# SCH_Star_blinking_2021-12-23.net
KiCad netlist of a schematic drawn in EasyEDA
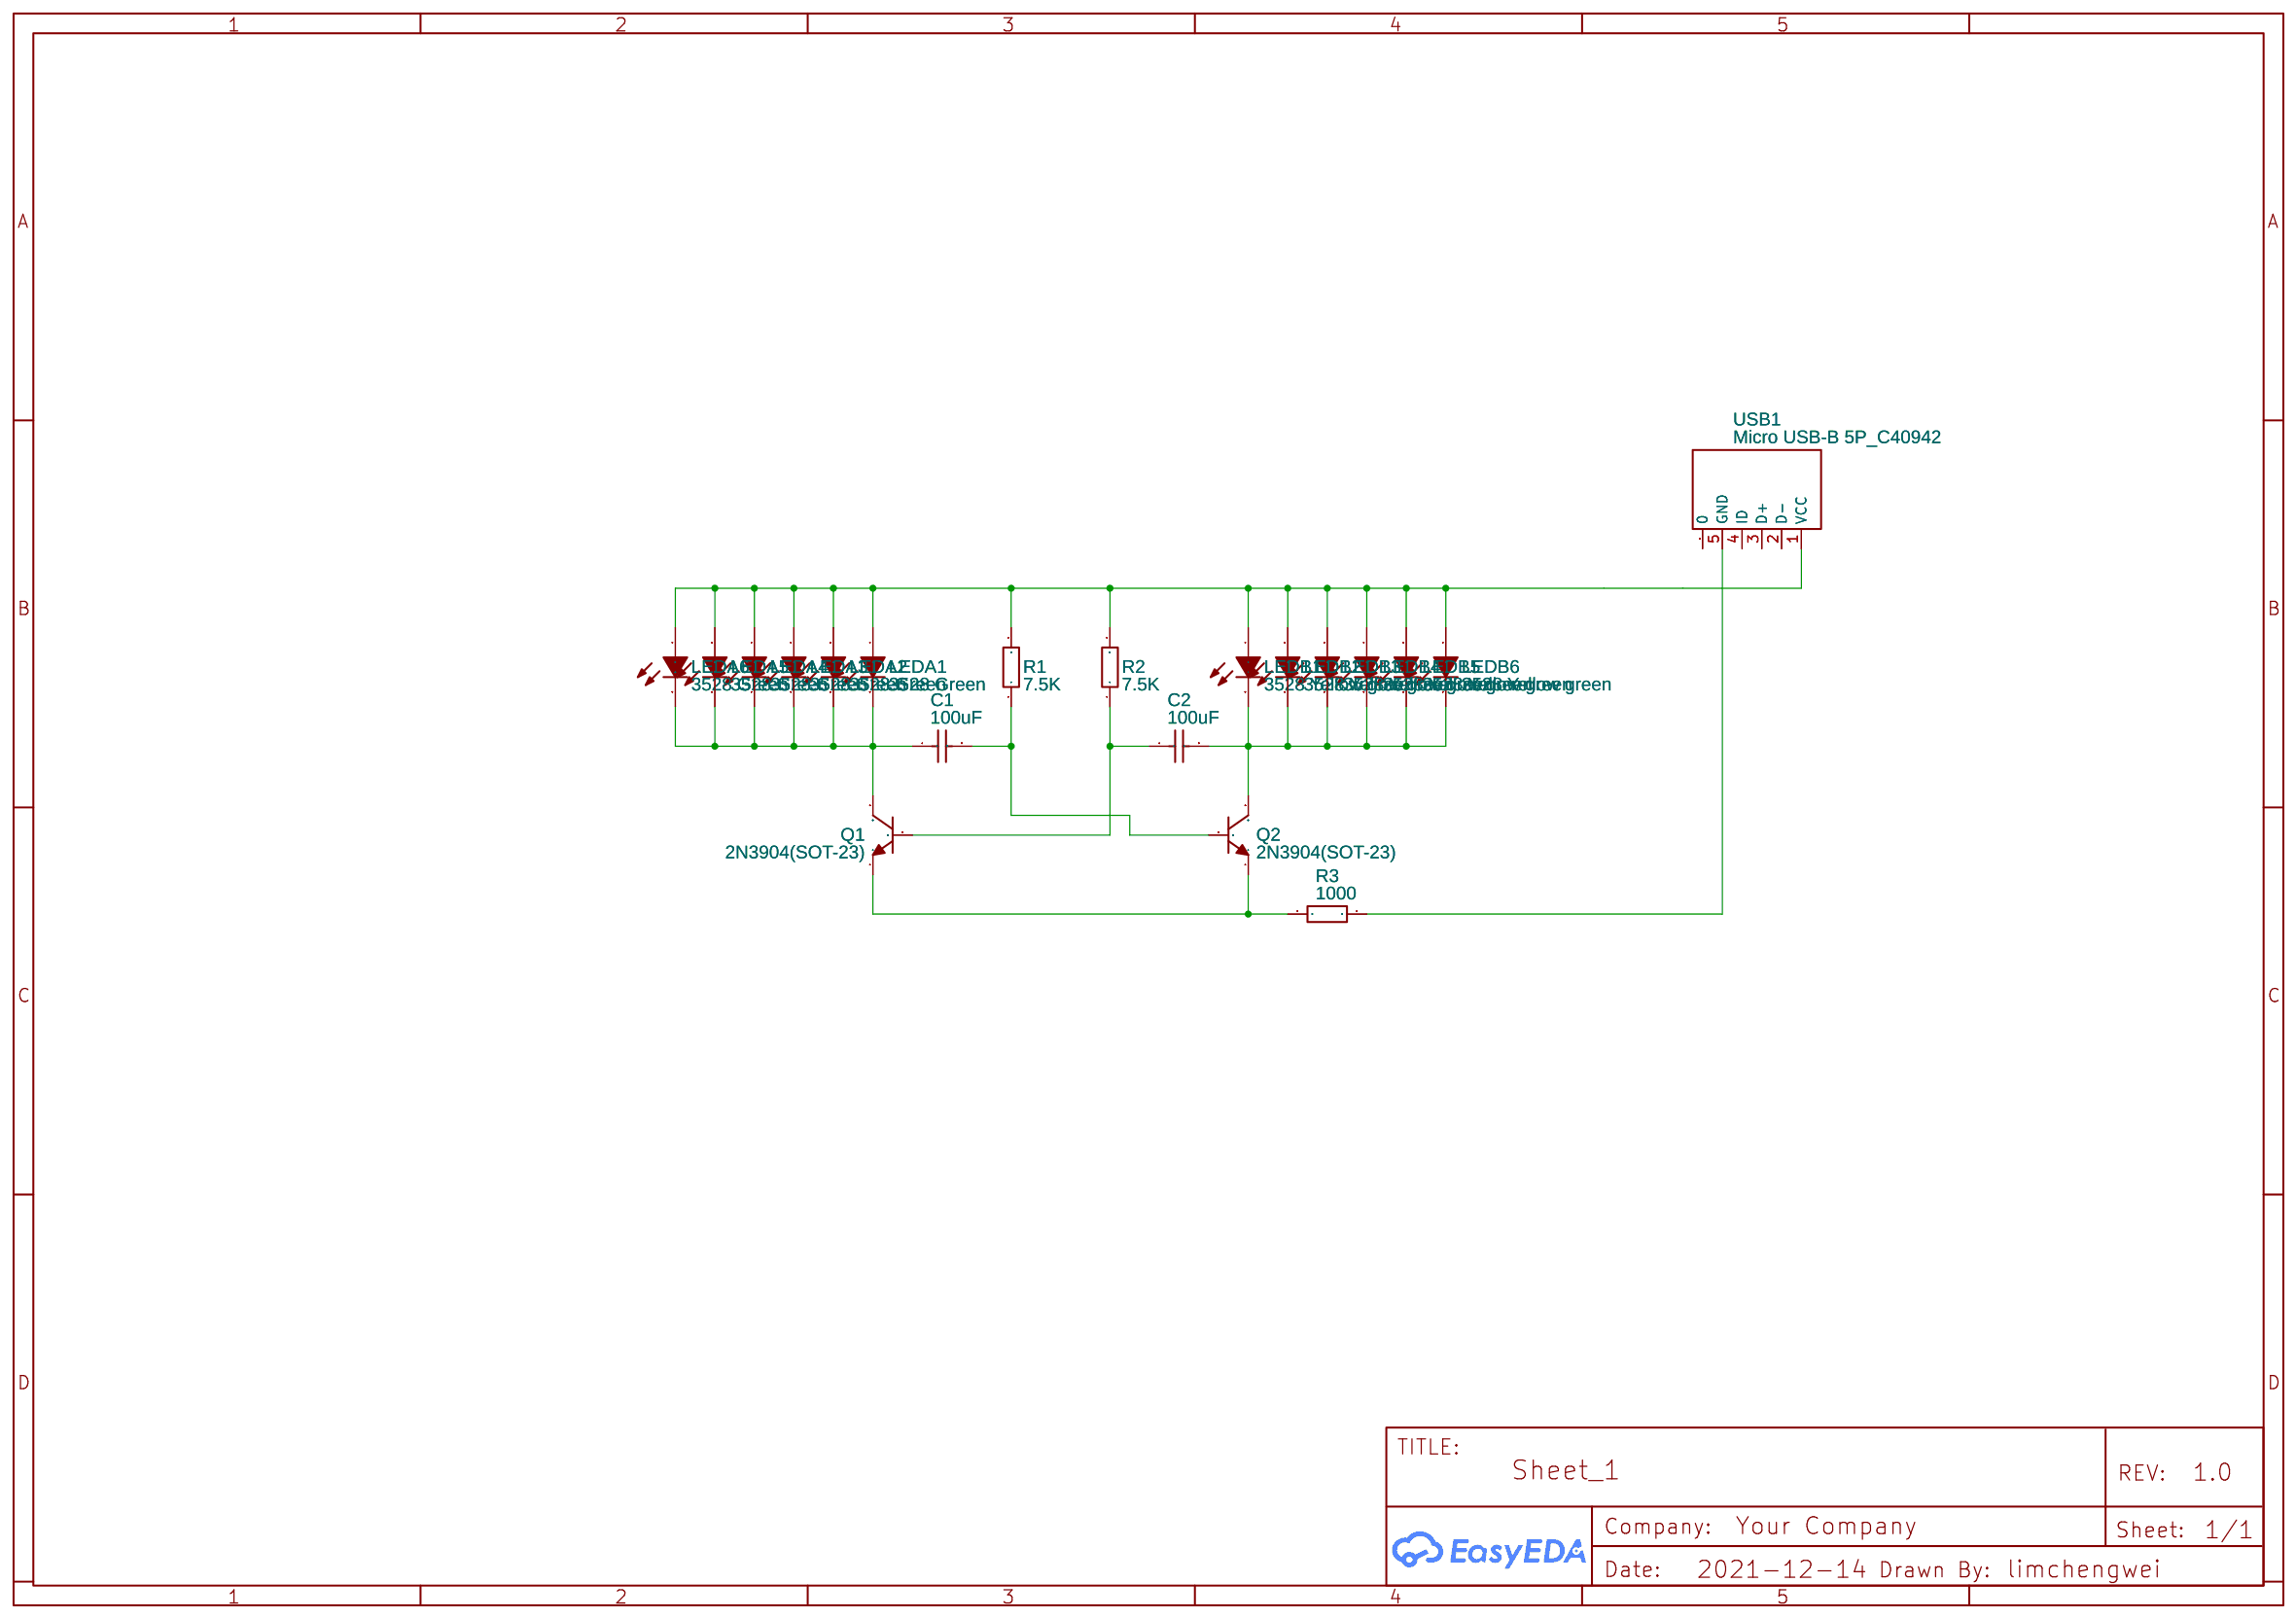
[diagram p0: schematic sheet]

(export (version "E")
  (design (tool "Eeschema 10.0.6"))
  (components
    (comp (ref "C1")
      (value "100uF")
      (fields
        (field (name "BOM_Manufacturer Part") "CL32A107MQVNNNE")
        (field (name "BOM_Supplier Part") "C49066")
      )
      (libsource (lib "") (part "CL32A107MQVNNNE"))
    )
    (comp (ref "C2")
      (value "100uF")
      (fields
        (field (name "BOM_Manufacturer Part") "CL32A107MQVNNNE")
        (field (name "BOM_Supplier Part") "C49066")
      )
      (libsource (lib "") (part "CL32A107MQVNNNE"))
    )
    (comp (ref "LEDA1")
      (value "3528 Green")
      (fields (field (name "BOM_Supplier Part") "C2308"))
      (libsource (lib "") (part "3528 Green"))
    )
    (comp (ref "LEDA2")
      (value "3528 Green")
      (fields (field (name "BOM_Supplier Part") "C2308"))
      (libsource (lib "") (part "3528 Green"))
    )
    (comp (ref "LEDA3")
      (value "3528 Green")
      (fields (field (name "BOM_Supplier Part") "C2308"))
      (libsource (lib "") (part "3528 Green"))
    )
    (comp (ref "LEDA4")
      (value "3528 Green")
      (fields (field (name "BOM_Supplier Part") "C2308"))
      (libsource (lib "") (part "3528 Green"))
    )
    (comp (ref "LEDA5")
      (value "3528 Green")
      (fields (field (name "BOM_Supplier Part") "C2308"))
      (libsource (lib "") (part "3528 Green"))
    )
    (comp (ref "LEDA6")
      (value "3528 Green")
      (fields (field (name "BOM_Supplier Part") "C2308"))
      (libsource (lib "") (part "3528 Green"))
    )
    (comp (ref "LEDB1")
      (value "3528 Yellow green")
      (fields (field (name "BOM_Supplier Part") "C2304"))
      (libsource (lib "") (part "3528 Yellow green"))
    )
    (comp (ref "LEDB2")
      (value "3528 Yellow green")
      (fields (field (name "BOM_Supplier Part") "C2304"))
      (libsource (lib "") (part "3528 Yellow green"))
    )
    (comp (ref "LEDB3")
      (value "3528 Yellow green")
      (fields (field (name "BOM_Supplier Part") "C2304"))
      (libsource (lib "") (part "3528 Yellow green"))
    )
    (comp (ref "LEDB4")
      (value "3528 Yellow green")
      (fields (field (name "BOM_Supplier Part") "C2304"))
      (libsource (lib "") (part "3528 Yellow green"))
    )
    (comp (ref "LEDB5")
      (value "3528 Yellow green")
      (fields (field (name "BOM_Supplier Part") "C2304"))
      (libsource (lib "") (part "3528 Yellow green"))
    )
    (comp (ref "LEDB6")
      (value "3528 Yellow green")
      (fields (field (name "BOM_Supplier Part") "C2304"))
      (libsource (lib "") (part "3528 Yellow green"))
    )
    (comp (ref "Q1")
      (value "2N3904(SOT-23)")
      (fields
        (field (name "BOM_Manufacturer Part") "2n3904S-RTK/PS")
        (field (name "BOM_Supplier Part") "C18536")
      )
      (libsource (lib "") (part "2N3904(SOT-23)_1"))
    )
    (comp (ref "Q2")
      (value "2N3904(SOT-23)")
      (fields
        (field (name "BOM_Manufacturer Part") "2n3904S-RTK/PS")
        (field (name "BOM_Supplier Part") "C18536")
      )
      (libsource (lib "") (part "2N3904(SOT-23)"))
    )
    (comp (ref "R1")
      (value "7.5K")
      (fields
        (field (name "BOM_Manufacturer Part") "1210W3J0752T5E")
        (field (name "BOM_Supplier Part") "C26065")
      )
      (libsource (lib "") (part "1210W3J0752T5E"))
    )
    (comp (ref "R2")
      (value "7.5K")
      (fields
        (field (name "BOM_Manufacturer Part") "1210W3J0752T5E")
        (field (name "BOM_Supplier Part") "C26065")
      )
      (libsource (lib "") (part "1210W3J0752T5E"))
    )
    (comp (ref "R3")
      (value "1000")
      (fields
        (field (name "BOM_Manufacturer Part") "1210W3J0752T5E")
        (field (name "BOM_Supplier Part") "C26065")
      )
      (libsource (lib "") (part "1210W3J0752T5E_1"))
    )
    (comp (ref "USB1")
      (value "Micro USB-B 5P_C40942")
      (fields (field (name "BOM_Supplier Part") "C40942"))
      (libsource (lib "") (part "Micro USB-B 5P_C40942"))
    )
  )
  (nets
    (net (code "1") (name "Net-(LEDA1-A)") (class "Default")
      (node (ref "LEDA1") (pin "1") (pinfunction "A_1") (pintype "input"))
      (node (ref "LEDA2") (pin "1") (pinfunction "A_1") (pintype "input"))
      (node (ref "LEDA3") (pin "1") (pinfunction "A_1") (pintype "input"))
      (node (ref "LEDA4") (pin "1") (pinfunction "A_1") (pintype "input"))
      (node (ref "LEDA5") (pin "1") (pinfunction "A_1") (pintype "input"))
      (node (ref "LEDA6") (pin "1") (pinfunction "A_1") (pintype "input"))
      (node (ref "LEDB1") (pin "1") (pinfunction "+_1") (pintype "input"))
      (node (ref "LEDB2") (pin "1") (pinfunction "+_1") (pintype "input"))
      (node (ref "LEDB3") (pin "1") (pinfunction "+_1") (pintype "input"))
      (node (ref "LEDB4") (pin "1") (pinfunction "+_1") (pintype "input"))
      (node (ref "LEDB5") (pin "1") (pinfunction "+_1") (pintype "input"))
      (node (ref "LEDB6") (pin "1") (pinfunction "+_1") (pintype "input"))
      (node (ref "R1") (pin "2") (pinfunction "2_2") (pintype "input"))
      (node (ref "R2") (pin "2") (pinfunction "2_2") (pintype "input"))
      (node (ref "USB1") (pin "1") (pinfunction "VCC_1") (pintype "input"))
    )
    (net (code "2") (name "Net-(LEDA1-C)") (class "Default")
      (node (ref "C1") (pin "1") (pinfunction "1_1") (pintype "input"))
      (node (ref "LEDA1") (pin "2") (pinfunction "C_2") (pintype "input"))
      (node (ref "LEDA2") (pin "2") (pinfunction "C_2") (pintype "input"))
      (node (ref "LEDA3") (pin "2") (pinfunction "C_2") (pintype "input"))
      (node (ref "LEDA4") (pin "2") (pinfunction "C_2") (pintype "input"))
      (node (ref "LEDA5") (pin "2") (pinfunction "C_2") (pintype "input"))
      (node (ref "LEDA6") (pin "2") (pinfunction "C_2") (pintype "input"))
      (node (ref "Q1") (pin "3") (pinfunction "C_3") (pintype "input"))
    )
    (net (code "3") (name "Net-(LEDB1--)") (class "Default")
      (node (ref "C2") (pin "2") (pinfunction "2_2") (pintype "input"))
      (node (ref "LEDB1") (pin "2") (pinfunction "-_2") (pintype "input"))
      (node (ref "LEDB2") (pin "2") (pinfunction "-_2") (pintype "input"))
      (node (ref "LEDB3") (pin "2") (pinfunction "-_2") (pintype "input"))
      (node (ref "LEDB4") (pin "2") (pinfunction "-_2") (pintype "input"))
      (node (ref "LEDB5") (pin "2") (pinfunction "-_2") (pintype "input"))
      (node (ref "LEDB6") (pin "2") (pinfunction "-_2") (pintype "input"))
      (node (ref "Q2") (pin "3") (pinfunction "C_3") (pintype "input"))
    )
    (net (code "4") (name "Net-(Q1-B)") (class "Default")
      (node (ref "C2") (pin "1") (pinfunction "1_1") (pintype "input"))
      (node (ref "Q1") (pin "2") (pinfunction "B_2") (pintype "input"))
      (node (ref "R2") (pin "1") (pinfunction "1_1") (pintype "input"))
    )
    (net (code "5") (name "Net-(Q1-E)") (class "Default")
      (node (ref "Q1") (pin "1") (pinfunction "E_1") (pintype "input"))
      (node (ref "Q2") (pin "1") (pinfunction "E_1") (pintype "input"))
      (node (ref "R3") (pin "2") (pinfunction "2_2") (pintype "input"))
    )
    (net (code "6") (name "Net-(Q2-B)") (class "Default")
      (node (ref "C1") (pin "2") (pinfunction "2_2") (pintype "input"))
      (node (ref "Q2") (pin "2") (pinfunction "B_2") (pintype "input"))
      (node (ref "R1") (pin "1") (pinfunction "1_1") (pintype "input"))
    )
    (net (code "7") (name "Net-(USB1-GND)") (class "Default")
      (node (ref "R3") (pin "1") (pinfunction "1_1") (pintype "input"))
      (node (ref "USB1") (pin "5") (pinfunction "GND_5") (pintype "input"))
    )
    (net (code "8") (name "unconnected-(USB1-D+-Pad3)") (class "Default")
      (node (ref "USB1") (pin "3") (pinfunction "D+_3") (pintype "input"))
    )
    (net (code "9") (name "unconnected-(USB1-D--Pad2)") (class "Default")
      (node (ref "USB1") (pin "2") (pinfunction "D-_2") (pintype "input"))
    )
    (net (code "10") (name "unconnected-(USB1-ID-Pad4)") (class "Default")
      (node (ref "USB1") (pin "4") (pinfunction "ID_4") (pintype "input"))
    )
    (net (code "11") (name "unconnected-(USB1-Pad0)") (class "Default")
      (node (ref "USB1") (pin "0") (pinfunction "0_0") (pintype "input"))
    )
  )
)
